# Amplifier2450.net
KiCad netlist of a schematic drawn in EAGLE
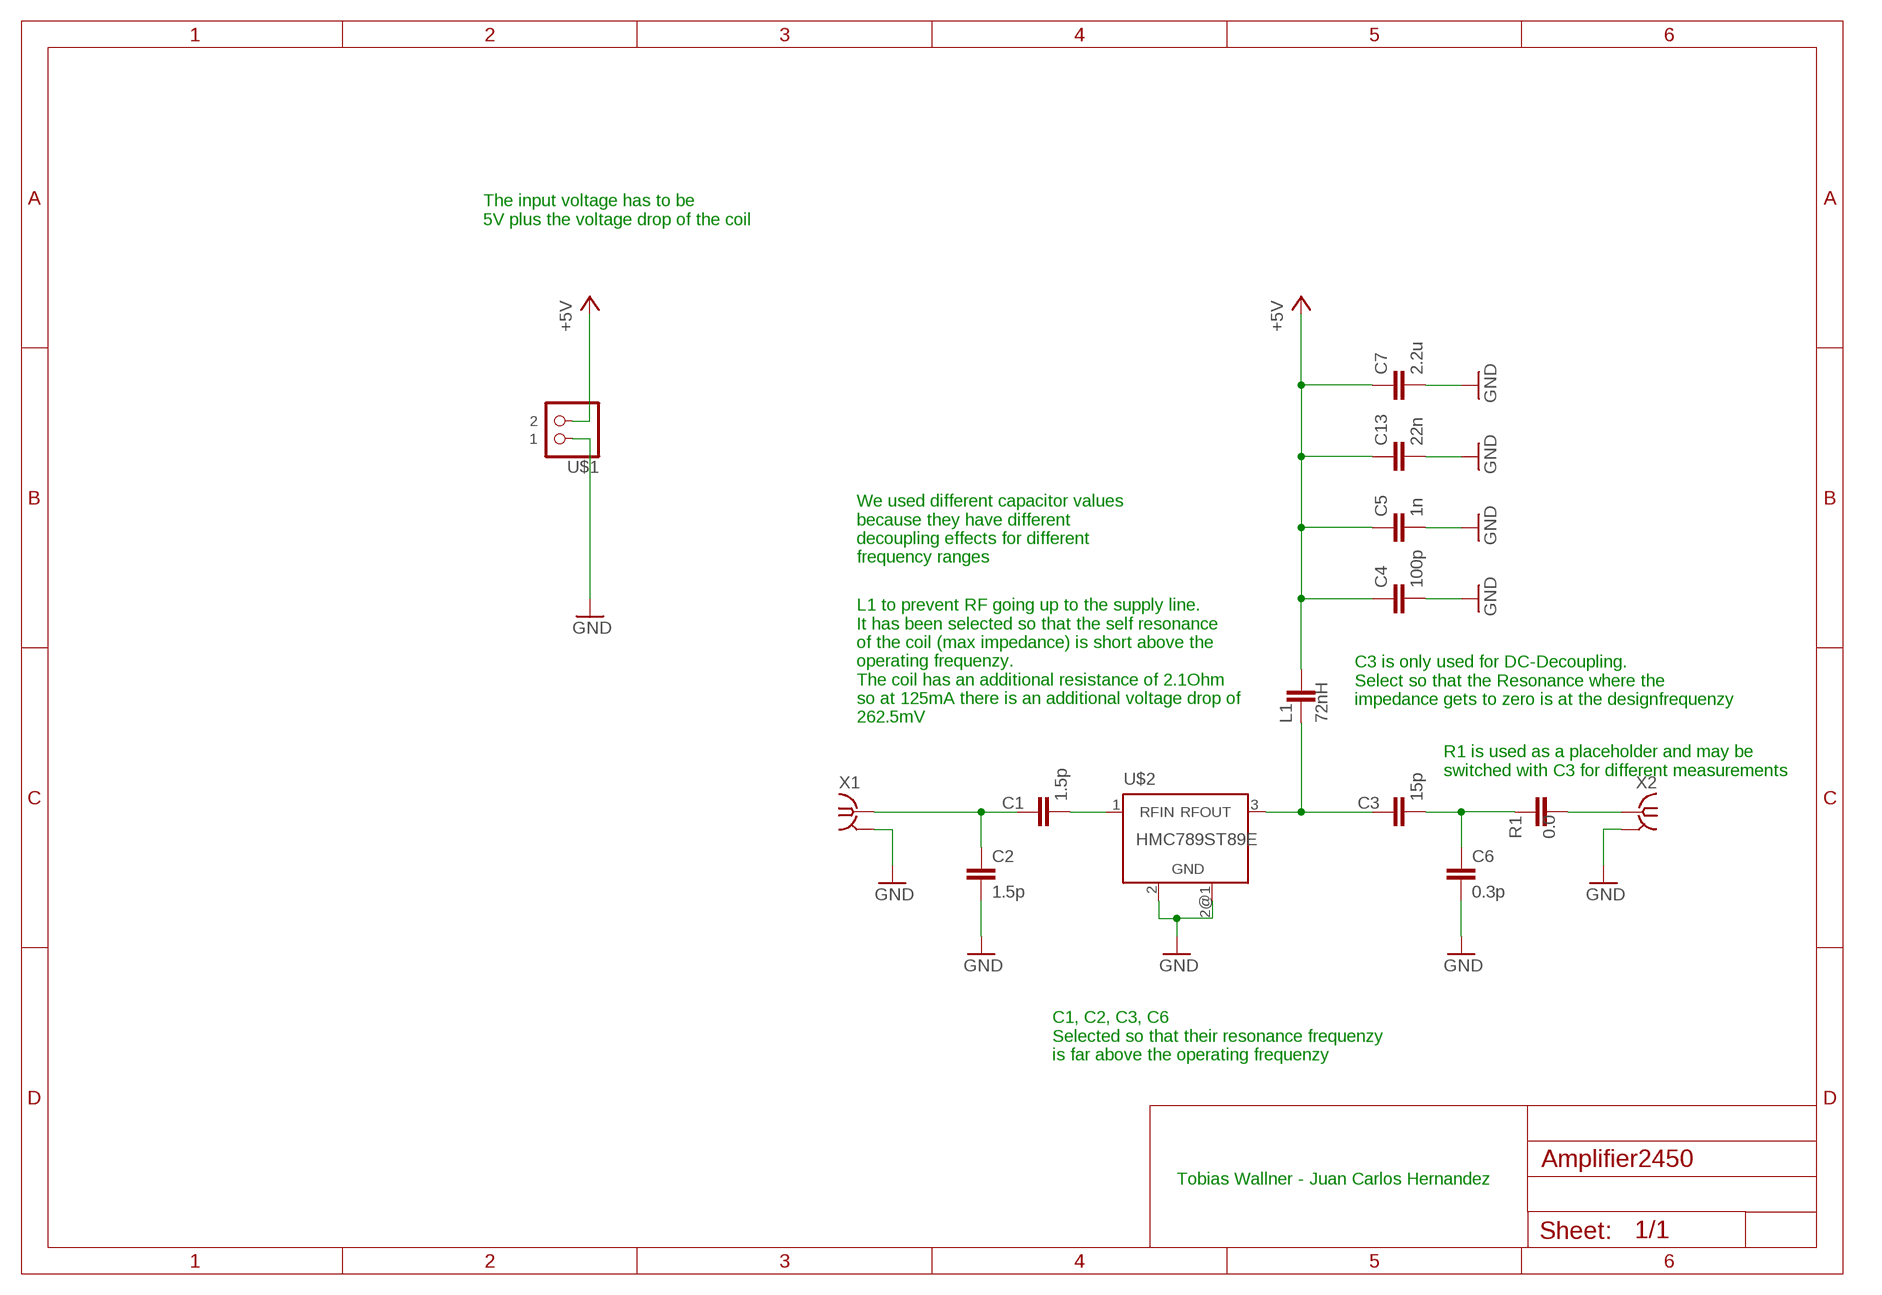
[diagram p0: schematic, sheet 1]

(export (version "E")
  (design (tool "Eeschema 10.0.6"))
  (components
    (comp (ref "C1")
      (value "1.5p")
      (footprint "eagle-import:C0603")
      (libsource (lib "eagle-import") (part "C-EUC0603"))
    )
    (comp (ref "C2")
      (value "1.5p")
      (footprint "eagle-import:C0603")
      (libsource (lib "eagle-import") (part "C-EUC0603"))
    )
    (comp (ref "C3")
      (value "15p")
      (footprint "eagle-import:C0603")
      (libsource (lib "eagle-import") (part "C-EUC0603"))
    )
    (comp (ref "C4")
      (value "100p")
      (footprint "eagle-import:C0603")
      (libsource (lib "eagle-import") (part "C-EUC0603"))
    )
    (comp (ref "C5")
      (value "1n")
      (footprint "eagle-import:C0603")
      (libsource (lib "eagle-import") (part "C-EUC0603"))
    )
    (comp (ref "C6")
      (value "0.3p")
      (footprint "eagle-import:C0603")
      (libsource (lib "eagle-import") (part "C-EUC0603"))
    )
    (comp (ref "C7")
      (value "2.2u")
      (footprint "eagle-import:C0805")
      (libsource (lib "eagle-import") (part "C-EUC0805"))
    )
    (comp (ref "C13")
      (value "22n")
      (footprint "eagle-import:C0603")
      (libsource (lib "eagle-import") (part "C-EUC0603"))
    )
    (comp (ref "L1")
      (value "72nH")
      (footprint "eagle-import:C0603")
      (libsource (lib "eagle-import") (part "C-EUC0603"))
    )
    (comp (ref "R1")
      (value "0.0")
      (footprint "eagle-import:C0603")
      (libsource (lib "eagle-import") (part "C-EUC0603"))
    )
    (comp (ref "U$1")
      (value "SKB_1X02_RM_5.12")
      (footprint "eagle-import:RM_5.12_1X02")
      (libsource (lib "eagle-import") (part "SKB_1X02_RM_5.12"))
    )
    (comp (ref "U$2")
      (value "HMC789ST89E")
      (footprint "eagle-import:SOT89")
      (libsource (lib "eagle-import") (part "HMC789ST89E"))
    )
    (comp (ref "X1")
      (value "SMA-142-0701-801/806")
      (footprint "eagle-import:J502-ND-142-0701-801_806")
      (fields (field (name "MF") "JOHNSON COMPONENTS") (field (name "MPN") "142-0701-801"))
      (libsource (lib "eagle-import") (part "SMA-142-0701-801/806"))
    )
    (comp (ref "X2")
      (value "SMA-142-0701-801/806")
      (footprint "eagle-import:J502-ND-142-0701-801_806")
      (fields (field (name "MF") "JOHNSON COMPONENTS") (field (name "MPN") "142-0701-801"))
      (libsource (lib "eagle-import") (part "SMA-142-0701-801/806"))
    )
  )
  (nets
    (net (code "1") (name "+5V") (class "Default")
      (node (ref "C13") (pin "1") (pinfunction "1_1") (pintype "passive"))
      (node (ref "C4") (pin "1") (pinfunction "1_1") (pintype "passive"))
      (node (ref "C5") (pin "1") (pinfunction "1_1") (pintype "passive"))
      (node (ref "C7") (pin "1") (pinfunction "1_1") (pintype "passive"))
      (node (ref "L1") (pin "1") (pinfunction "1_1") (pintype "passive"))
      (node (ref "U$1") (pin "P$2") (pinfunction "2_P$2") (pintype "passive"))
    )
    (net (code "2") (name "GND") (class "Default")
      (node (ref "C13") (pin "2") (pinfunction "2_2") (pintype "passive"))
      (node (ref "C2") (pin "2") (pinfunction "2_2") (pintype "passive"))
      (node (ref "C4") (pin "2") (pinfunction "2_2") (pintype "passive"))
      (node (ref "C5") (pin "2") (pinfunction "2_2") (pintype "passive"))
      (node (ref "C6") (pin "2") (pinfunction "2_2") (pintype "passive"))
      (node (ref "C7") (pin "2") (pinfunction "2_2") (pintype "passive"))
      (node (ref "U$1") (pin "P$1") (pinfunction "1_P$1") (pintype "passive"))
      (node (ref "U$2") (pin "2") (pinfunction "GND_2") (pintype "power_in"))
      (node (ref "U$2") (pin "2@1") (pinfunction "GND_2@1") (pintype "power_in"))
      (node (ref "X1") (pin "G@1") (pinfunction "2_G@1") (pintype "passive"))
      (node (ref "X1") (pin "G@2") (pinfunction "2_G@2") (pintype "passive"))
      (node (ref "X1") (pin "G@3") (pinfunction "2_G@3") (pintype "passive"))
      (node (ref "X1") (pin "G@4") (pinfunction "2_G@4") (pintype "passive"))
      (node (ref "X2") (pin "G@1") (pinfunction "2_G@1") (pintype "passive"))
      (node (ref "X2") (pin "G@2") (pinfunction "2_G@2") (pintype "passive"))
      (node (ref "X2") (pin "G@3") (pinfunction "2_G@3") (pintype "passive"))
      (node (ref "X2") (pin "G@4") (pinfunction "2_G@4") (pintype "passive"))
    )
    (net (code "3") (name "Net-(C1-Pad1)") (class "Default")
      (node (ref "C1") (pin "1") (pinfunction "1_1") (pintype "passive"))
      (node (ref "C2") (pin "1") (pinfunction "1_1") (pintype "passive"))
      (node (ref "X1") (pin "1") (pinfunction "1_1") (pintype "passive"))
    )
    (net (code "4") (name "Net-(C3-Pad2)") (class "Default")
      (node (ref "C3") (pin "2") (pinfunction "2_2") (pintype "passive"))
      (node (ref "C6") (pin "1") (pinfunction "1_1") (pintype "passive"))
      (node (ref "R1") (pin "1") (pinfunction "1_1") (pintype "passive"))
    )
    (net (code "5") (name "Net-(R1-Pad2)") (class "Default")
      (node (ref "R1") (pin "2") (pinfunction "2_2") (pintype "passive"))
      (node (ref "X2") (pin "1") (pinfunction "1_1") (pintype "passive"))
    )
    (net (code "6") (name "Net-(U$2-RFIN)") (class "Default")
      (node (ref "C1") (pin "2") (pinfunction "2_2") (pintype "passive"))
      (node (ref "U$2") (pin "1") (pinfunction "RFIN_1") (pintype "passive"))
    )
    (net (code "7") (name "Net-(U$2-RFOUT)") (class "Default")
      (node (ref "C3") (pin "1") (pinfunction "1_1") (pintype "passive"))
      (node (ref "L1") (pin "2") (pinfunction "2_2") (pintype "passive"))
      (node (ref "U$2") (pin "3") (pinfunction "RFOUT_3") (pintype "output"))
    )
  )
)
